# SCH.net
KiCad netlist of a schematic drawn in EasyEDA
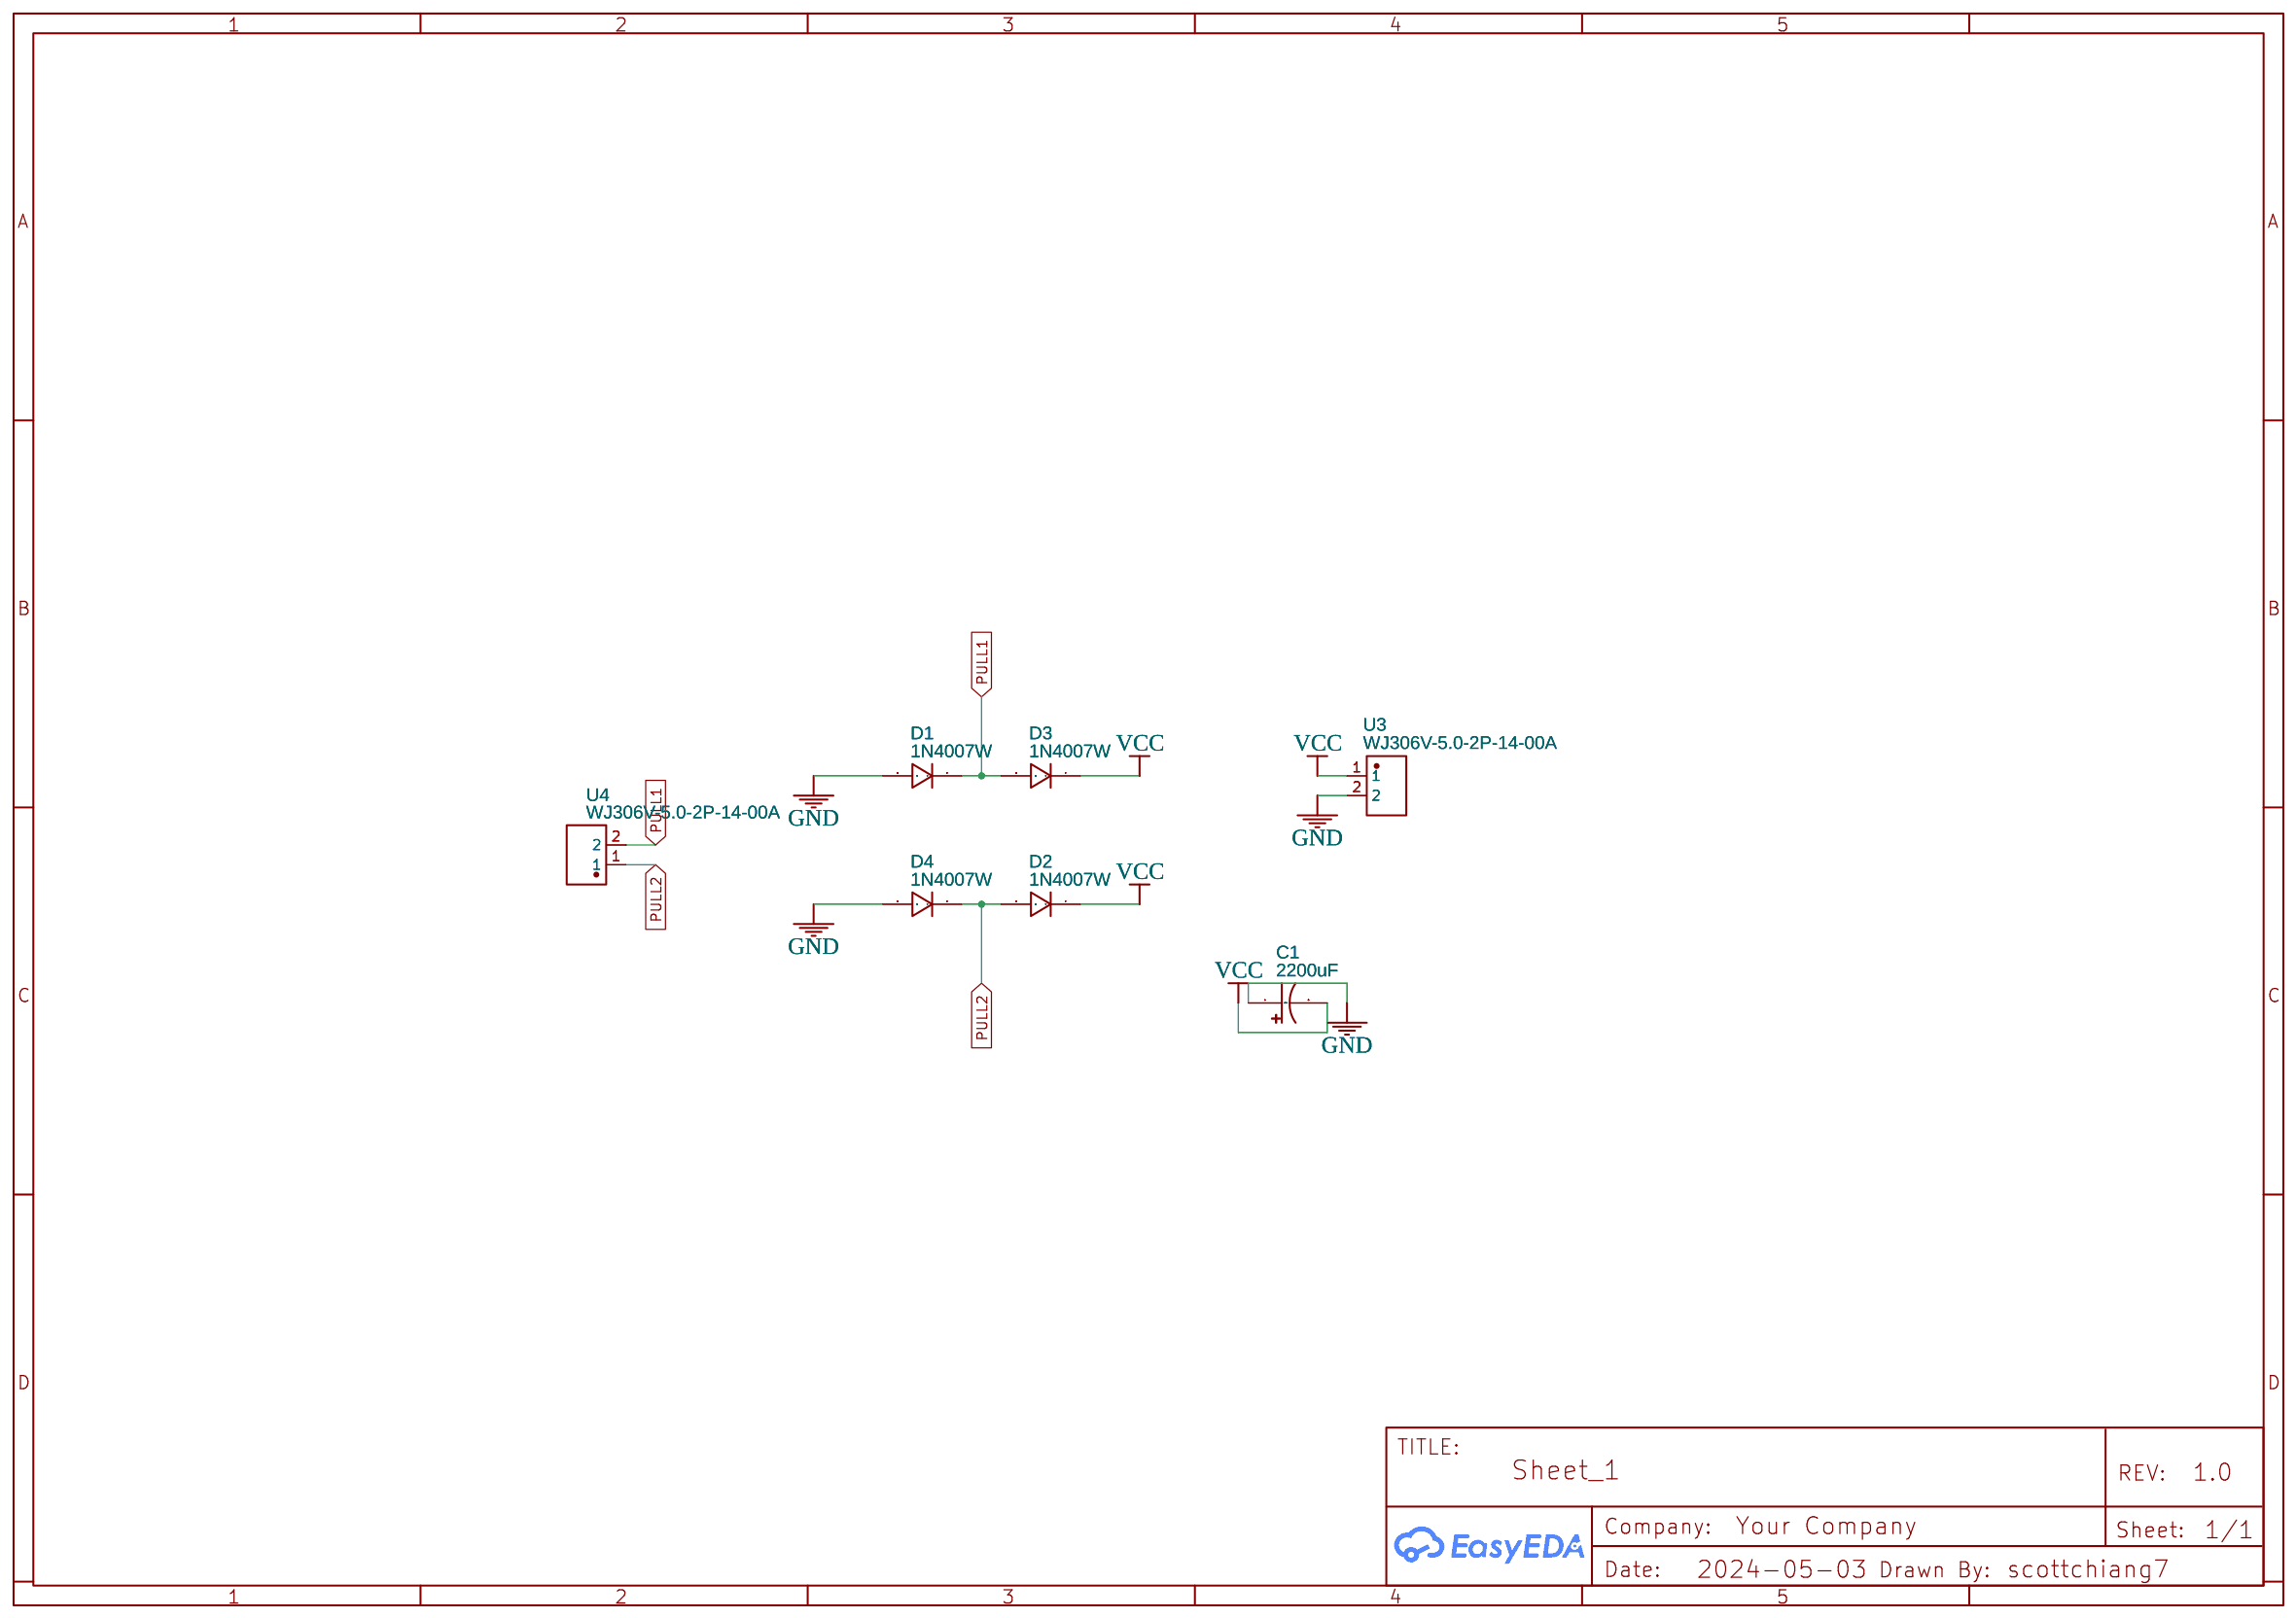
[diagram p0: schematic sheet]

(export (version "E")
  (design (tool "Eeschema 10.0.6"))
  (components
    (comp (ref "C1")
      (value "2200uF")
      (fields
        (field (name "Manufacturer Part") "25YXA2200MEFCCE12.5X25")
        (field (name "Manufacturer") "rubycon(红宝石)")
      )
      (libsource (lib "") (part "25YXA2200MEFCCE12.5X25"))
    )
    (comp (ref "D1")
      (value "1N4007W")
      (fields (field (name "Manufacturer") "BLUE ROCKET"))
      (libsource (lib "") (part "1N4007W"))
    )
    (comp (ref "D2")
      (value "1N4007W")
      (fields (field (name "Manufacturer") "BLUE ROCKET"))
      (libsource (lib "") (part "1N4007W"))
    )
    (comp (ref "D3")
      (value "1N4007W")
      (fields (field (name "Manufacturer") "BLUE ROCKET"))
      (libsource (lib "") (part "1N4007W"))
    )
    (comp (ref "D4")
      (value "1N4007W")
      (fields (field (name "Manufacturer") "BLUE ROCKET"))
      (libsource (lib "") (part "1N4007W"))
    )
    (comp (ref "U3")
      (value "WJ306V-5.0-2P-14-00A")
      (fields (field (name "Manufacturer") "KANGNEX(康奈克斯电气)"))
      (libsource (lib "") (part "WJ306V-5.0-2P-14-00A_1"))
    )
    (comp (ref "U4")
      (value "WJ306V-5.0-2P-14-00A")
      (fields (field (name "Manufacturer") "KANGNEX(康奈克斯电气)"))
      (libsource (lib "") (part "WJ306V-5.0-2P-14-00A"))
    )
  )
  (nets
    (net (code "1") (name "GND") (class "Default")
      (node (ref "C1") (pin "1") (pinfunction "1_1") (pintype "unspecified"))
      (node (ref "D1") (pin "2") (pinfunction "2_2") (pintype "unspecified"))
      (node (ref "D4") (pin "2") (pinfunction "2_2") (pintype "unspecified"))
      (node (ref "U3") (pin "2") (pinfunction "2_2") (pintype "unspecified"))
    )
    (net (code "2") (name "PULL1") (class "Default")
      (node (ref "D1") (pin "1") (pinfunction "1_1") (pintype "unspecified"))
      (node (ref "D3") (pin "2") (pinfunction "2_2") (pintype "unspecified"))
      (node (ref "U4") (pin "2") (pinfunction "2_2") (pintype "unspecified"))
    )
    (net (code "3") (name "PULL2") (class "Default")
      (node (ref "D2") (pin "2") (pinfunction "2_2") (pintype "unspecified"))
      (node (ref "D4") (pin "1") (pinfunction "1_1") (pintype "unspecified"))
      (node (ref "U4") (pin "1") (pinfunction "1_1") (pintype "unspecified"))
    )
    (net (code "4") (name "VCC") (class "Default")
      (node (ref "C1") (pin "2") (pinfunction "2_2") (pintype "unspecified"))
      (node (ref "D2") (pin "1") (pinfunction "1_1") (pintype "unspecified"))
      (node (ref "D3") (pin "1") (pinfunction "1_1") (pintype "unspecified"))
      (node (ref "U3") (pin "1") (pinfunction "1_1") (pintype "unspecified"))
    )
  )
)
